# RDA1846.net
KiCad netlist of a schematic drawn in EAGLE
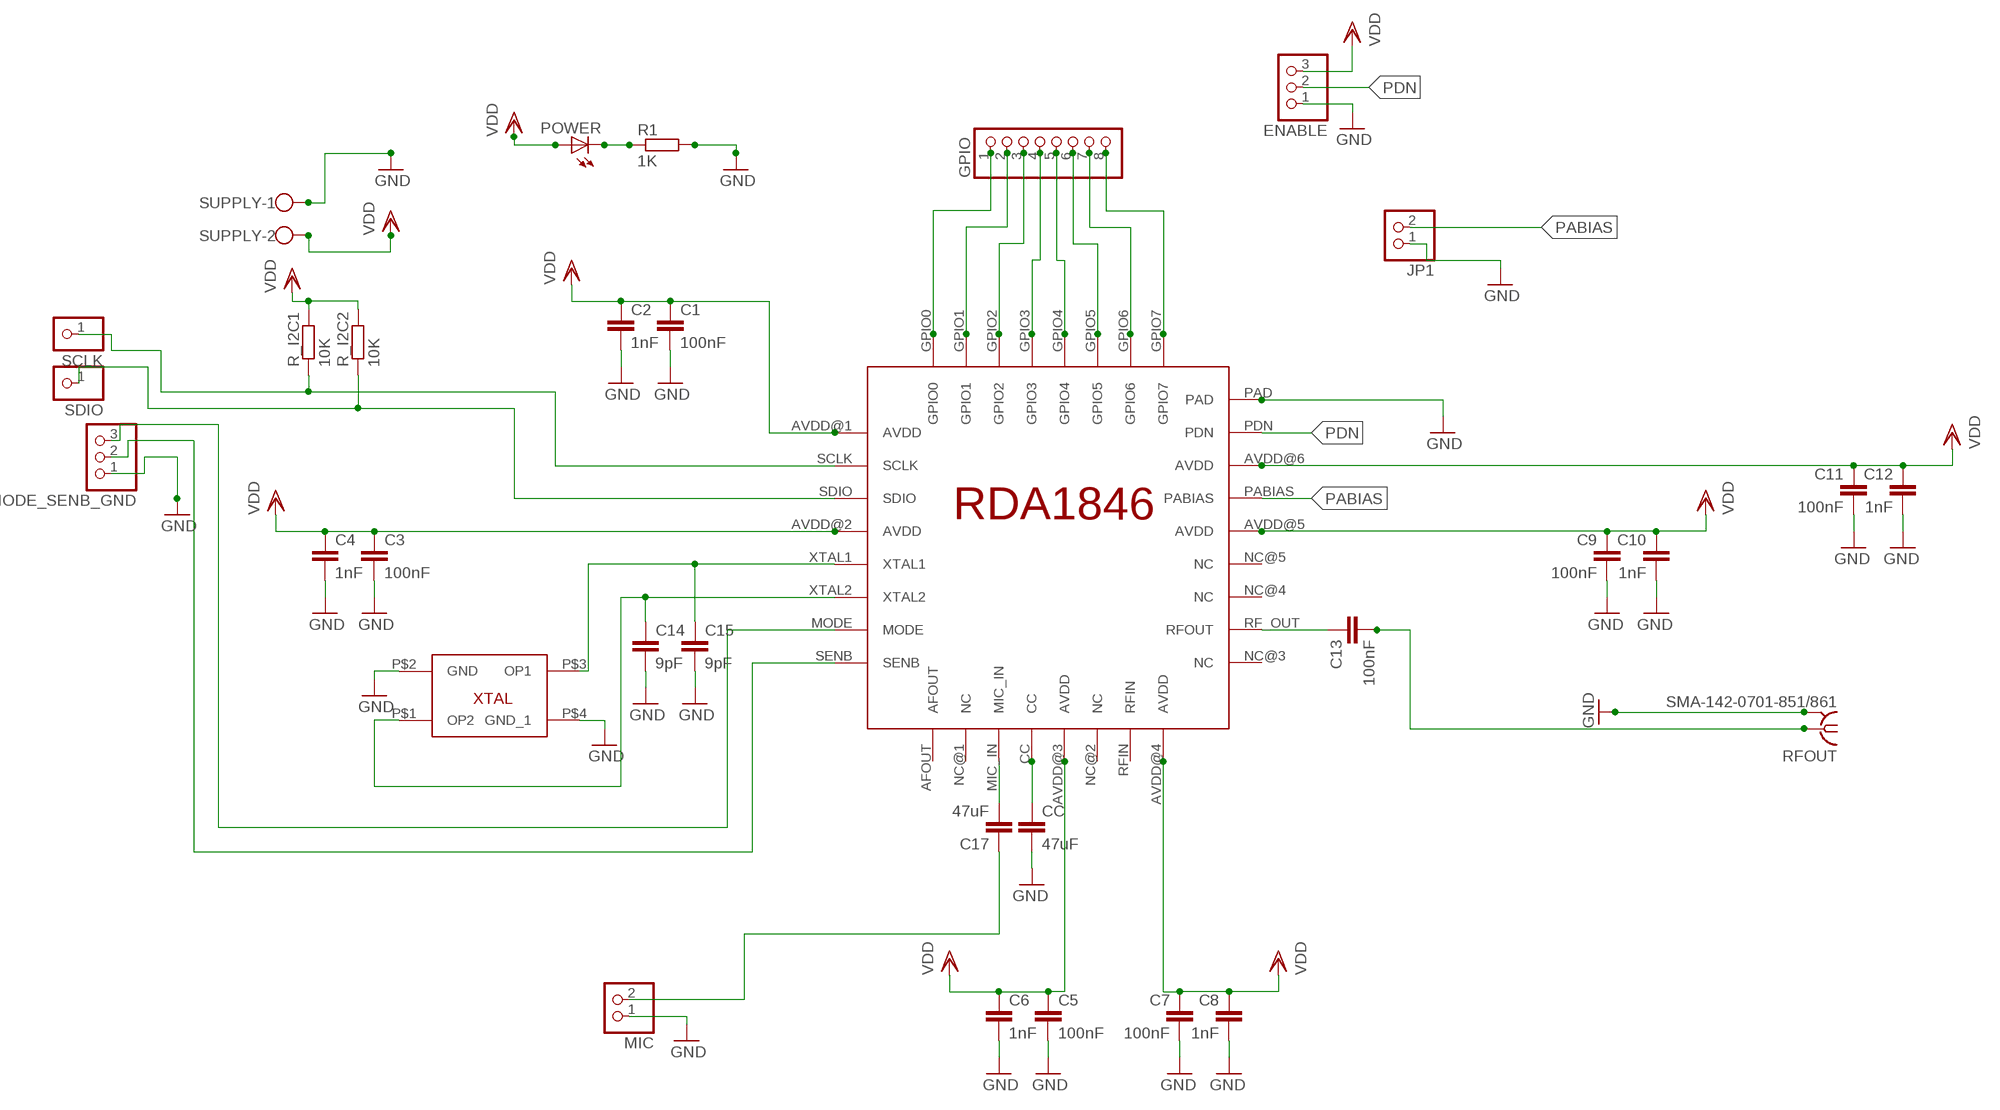
[diagram p0: schematic, sheet 1]
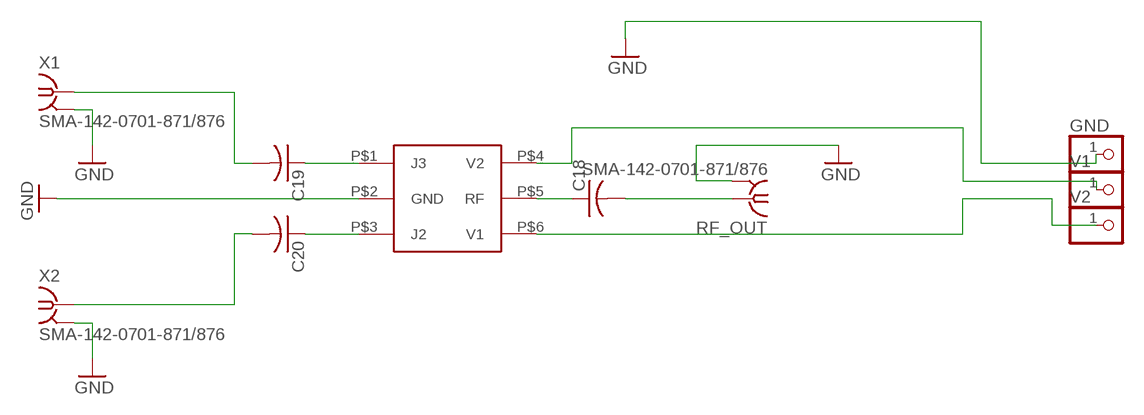
[diagram p1: schematic, sheet 2]

(export (version "E")
  (design (tool "Eeschema 10.0.6"))
  (components
    (comp (ref "C1")
      (value "100nF")
      (footprint "eagle-import:C0805")
      (libsource (lib "eagle-import") (part "C-EUC0805"))
    )
    (comp (ref "C2")
      (value "1nF")
      (footprint "eagle-import:C0805")
      (libsource (lib "eagle-import") (part "C-EUC0805"))
    )
    (comp (ref "C3")
      (value "100nF")
      (footprint "eagle-import:C0805")
      (libsource (lib "eagle-import") (part "C-EUC0805"))
    )
    (comp (ref "C4")
      (value "1nF")
      (footprint "eagle-import:C0805")
      (libsource (lib "eagle-import") (part "C-EUC0805"))
    )
    (comp (ref "C5")
      (value "100nF")
      (footprint "eagle-import:C0805")
      (libsource (lib "eagle-import") (part "C-EUC0805"))
    )
    (comp (ref "C6")
      (value "1nF")
      (footprint "eagle-import:C0805")
      (libsource (lib "eagle-import") (part "C-EUC0805"))
    )
    (comp (ref "C7")
      (value "100nF")
      (footprint "eagle-import:C0805")
      (libsource (lib "eagle-import") (part "C-EUC0805"))
    )
    (comp (ref "C8")
      (value "1nF")
      (footprint "eagle-import:C0805")
      (libsource (lib "eagle-import") (part "C-EUC0805"))
    )
    (comp (ref "C9")
      (value "100nF")
      (footprint "eagle-import:C0805")
      (libsource (lib "eagle-import") (part "C-EUC0805"))
    )
    (comp (ref "C10")
      (value "1nF")
      (footprint "eagle-import:C0805")
      (libsource (lib "eagle-import") (part "C-EUC0805"))
    )
    (comp (ref "C11")
      (value "100nF")
      (footprint "eagle-import:C0805")
      (libsource (lib "eagle-import") (part "C-EUC0805"))
    )
    (comp (ref "C12")
      (value "1nF")
      (footprint "eagle-import:C0805")
      (libsource (lib "eagle-import") (part "C-EUC0805"))
    )
    (comp (ref "C13")
      (value "100nF")
      (footprint "eagle-import:C0805")
      (libsource (lib "eagle-import") (part "C-EUC0805"))
    )
    (comp (ref "C14")
      (value "9pF")
      (footprint "eagle-import:C0805")
      (libsource (lib "eagle-import") (part "C-EUC0805"))
    )
    (comp (ref "C15")
      (value "9pF")
      (footprint "eagle-import:C0805")
      (libsource (lib "eagle-import") (part "C-EUC0805"))
    )
    (comp (ref "C17")
      (value "47uF")
      (footprint "eagle-import:C0805")
      (libsource (lib "eagle-import") (part "C-EUC0805"))
    )
    (comp (ref "CC")
      (value "47uF")
      (footprint "eagle-import:C0805")
      (libsource (lib "eagle-import") (part "C-EUC0805"))
    )
    (comp (ref "ENABLE")
      (value "PINHD-1X3")
      (footprint "eagle-import:1X03")
      (libsource (lib "eagle-import") (part "PINHD-1X3"))
    )
    (comp (ref "GPIO")
      (value "PINHD-1X8CLEANBIG")
      (footprint "eagle-import:1X08-CLEANBIG")
      (libsource (lib "eagle-import") (part "PINHD-1X8CLEANBIG"))
    )
    (comp (ref "JP1")
      (value "PINHD-1X2")
      (footprint "eagle-import:1X02")
      (libsource (lib "eagle-import") (part "PINHD-1X2"))
    )
    (comp (ref "MIC")
      (value "PINHD-1X2")
      (footprint "eagle-import:1X02")
      (libsource (lib "eagle-import") (part "PINHD-1X2"))
    )
    (comp (ref "MODE_SENB_GND")
      (value "PINHD-1X3")
      (footprint "eagle-import:1X03")
      (libsource (lib "eagle-import") (part "PINHD-1X3"))
    )
    (comp (ref "POWER")
      (value "LEDCHIPLED_1206")
      (footprint "eagle-import:CHIPLED_1206")
      (libsource (lib "eagle-import") (part "LEDCHIPLED_1206"))
    )
    (comp (ref "R1")
      (value "1K")
      (footprint "eagle-import:R0805")
      (libsource (lib "eagle-import") (part "R-EU_R0805"))
    )
    (comp (ref "RFOUT")
      (value "SMA-142-0701-851/861")
      (footprint "eagle-import:J502-ND-142-0701-851_861")
      (fields (field (name "MF") "JOHNSON COMPONENTS") (field (name "MPN") "142-0701-851"))
      (libsource (lib "eagle-import") (part "SMA-142-0701-851/861"))
    )
    (comp (ref "R_I2C1")
      (value "10K")
      (footprint "eagle-import:R0805")
      (libsource (lib "eagle-import") (part "R-EU_R0805"))
    )
    (comp (ref "R_I2C2")
      (value "10K")
      (footprint "eagle-import:R0805")
      (libsource (lib "eagle-import") (part "R-EU_R0805"))
    )
    (comp (ref "SCLK")
      (value "PINHD-1X1")
      (footprint "eagle-import:1X01")
      (libsource (lib "eagle-import") (part "PINHD-1X1"))
    )
    (comp (ref "SDIO")
      (value "PINHD-1X1")
      (footprint "eagle-import:1X01")
      (libsource (lib "eagle-import") (part "PINHD-1X1"))
    )
    (comp (ref "SUPPLY")
      (value "W237-102")
      (footprint "eagle-import:W237-102")
      (fields (field (name "MPN") "237-102"))
      (libsource (lib "eagle-import") (part "W237-102"))
    )
    (comp (ref "U$1")
      (value "RDA1846")
      (footprint "eagle-import:32_PIN_QFN")
      (libsource (lib "eagle-import") (part "RDA1846"))
    )
    (comp (ref "U$2")
      (value "CRYSTAL_FA_128")
      (footprint "eagle-import:FA_128")
      (libsource (lib "eagle-import") (part "CRYSTAL_FA_128"))
    )
    (comp (ref "C18")
      (value "C-USC1206")
      (footprint "eagle-import:C1206")
      (libsource (lib "eagle-import") (part "C-USC1206"))
    )
    (comp (ref "C19")
      (value "C-USC1206")
      (footprint "eagle-import:C1206")
      (libsource (lib "eagle-import") (part "C-USC1206"))
    )
    (comp (ref "C20")
      (value "C-USC1206")
      (footprint "eagle-import:C1206")
      (libsource (lib "eagle-import") (part "C-USC1206"))
    )
    (comp (ref "GND")
      (value "PINHD-1X1")
      (footprint "eagle-import:1X01")
      (libsource (lib "eagle-import") (part "pinhead_PINHD-1X1"))
    )
    (comp (ref "RF_OUT")
      (value "SMA-142-0701-871/876")
      (footprint "eagle-import:J502-ND-142-0701-871_876")
      (fields (field (name "MF") "JOHNSON COMPONENTS") (field (name "MPN") "142-0701-871"))
      (libsource (lib "eagle-import") (part "SMA-142-0701-871/876"))
    )
    (comp (ref "U$3")
      (value "RF_SWITCH")
      (footprint "eagle-import:SC90")
      (libsource (lib "eagle-import") (part "RF_SWITCH"))
    )
    (comp (ref "V1")
      (value "PINHD-1X1")
      (footprint "eagle-import:1X01")
      (libsource (lib "eagle-import") (part "pinhead_PINHD-1X1"))
    )
    (comp (ref "V2")
      (value "PINHD-1X1")
      (footprint "eagle-import:1X01")
      (libsource (lib "eagle-import") (part "pinhead_PINHD-1X1"))
    )
    (comp (ref "X1")
      (value "SMA-142-0701-871/876")
      (footprint "eagle-import:J502-ND-142-0701-871_876")
      (fields (field (name "MF") "JOHNSON COMPONENTS") (field (name "MPN") "142-0701-871"))
      (libsource (lib "eagle-import") (part "SMA-142-0701-871/876"))
    )
    (comp (ref "X2")
      (value "SMA-142-0701-871/876")
      (footprint "eagle-import:J502-ND-142-0701-871_876")
      (fields (field (name "MF") "JOHNSON COMPONENTS") (field (name "MPN") "142-0701-871"))
      (libsource (lib "eagle-import") (part "SMA-142-0701-871/876"))
    )
  )
  (nets
    (net (code "1") (name "GND") (class "Default")
      (node (ref "C1") (pin "2") (pinfunction "2_2") (pintype "passive"))
      (node (ref "C10") (pin "2") (pinfunction "2_2") (pintype "passive"))
      (node (ref "C11") (pin "2") (pinfunction "2_2") (pintype "passive"))
      (node (ref "C12") (pin "2") (pinfunction "2_2") (pintype "passive"))
      (node (ref "C14") (pin "2") (pinfunction "2_2") (pintype "passive"))
      (node (ref "C15") (pin "2") (pinfunction "2_2") (pintype "passive"))
      (node (ref "C2") (pin "2") (pinfunction "2_2") (pintype "passive"))
      (node (ref "C3") (pin "2") (pinfunction "2_2") (pintype "passive"))
      (node (ref "C4") (pin "2") (pinfunction "2_2") (pintype "passive"))
      (node (ref "C5") (pin "2") (pinfunction "2_2") (pintype "passive"))
      (node (ref "C6") (pin "2") (pinfunction "2_2") (pintype "passive"))
      (node (ref "C7") (pin "2") (pinfunction "2_2") (pintype "passive"))
      (node (ref "C8") (pin "2") (pinfunction "2_2") (pintype "passive"))
      (node (ref "C9") (pin "2") (pinfunction "2_2") (pintype "passive"))
      (node (ref "CC") (pin "2") (pinfunction "2_2") (pintype "passive"))
      (node (ref "ENABLE") (pin "1") (pinfunction "1_1") (pintype "passive"))
      (node (ref "GND") (pin "1") (pinfunction "1_1") (pintype "passive"))
      (node (ref "JP1") (pin "1") (pinfunction "1_1") (pintype "passive"))
      (node (ref "MIC") (pin "1") (pinfunction "1_1") (pintype "passive"))
      (node (ref "MODE_SENB_GND") (pin "1") (pinfunction "1_1") (pintype "passive"))
      (node (ref "R1") (pin "2") (pinfunction "2_2") (pintype "passive"))
      (node (ref "RFOUT") (pin "G@1") (pinfunction "2_G@1") (pintype "passive"))
      (node (ref "RFOUT") (pin "G@2") (pinfunction "2_G@2") (pintype "passive"))
      (node (ref "RFOUT") (pin "G@3") (pinfunction "2_G@3") (pintype "passive"))
      (node (ref "RFOUT") (pin "G@4") (pinfunction "2_G@4") (pintype "passive"))
      (node (ref "RF_OUT") (pin "G@1") (pinfunction "2_G@1") (pintype "passive"))
      (node (ref "RF_OUT") (pin "G@2") (pinfunction "2_G@2") (pintype "passive"))
      (node (ref "RF_OUT") (pin "G@3") (pinfunction "2_G@3") (pintype "passive"))
      (node (ref "RF_OUT") (pin "G@4") (pinfunction "2_G@4") (pintype "passive"))
      (node (ref "SUPPLY") (pin "1") (pinfunction "KL_1") (pintype "passive"))
      (node (ref "U$1") (pin "PAD") (pinfunction "PAD_PAD") (pintype "bidirectional"))
      (node (ref "U$2") (pin "P$2") (pinfunction "GND_P$2") (pintype "bidirectional"))
      (node (ref "U$2") (pin "P$4") (pinfunction "GND_1_P$4") (pintype "bidirectional"))
      (node (ref "U$3") (pin "P$2") (pinfunction "GND_P$2") (pintype "bidirectional"))
      (node (ref "X1") (pin "G@1") (pinfunction "2_G@1") (pintype "passive"))
      (node (ref "X1") (pin "G@2") (pinfunction "2_G@2") (pintype "passive"))
      (node (ref "X1") (pin "G@3") (pinfunction "2_G@3") (pintype "passive"))
      (node (ref "X1") (pin "G@4") (pinfunction "2_G@4") (pintype "passive"))
      (node (ref "X2") (pin "G@1") (pinfunction "2_G@1") (pintype "passive"))
      (node (ref "X2") (pin "G@2") (pinfunction "2_G@2") (pintype "passive"))
      (node (ref "X2") (pin "G@3") (pinfunction "2_G@3") (pintype "passive"))
      (node (ref "X2") (pin "G@4") (pinfunction "2_G@4") (pintype "passive"))
    )
    (net (code "2") (name "Net-(C13-Pad2)") (class "Default")
      (node (ref "C13") (pin "2") (pinfunction "2_2") (pintype "passive"))
      (node (ref "RFOUT") (pin "1") (pinfunction "1_1") (pintype "passive"))
    )
    (net (code "3") (name "Net-(C17-Pad1)") (class "Default")
      (node (ref "C17") (pin "1") (pinfunction "1_1") (pintype "passive"))
      (node (ref "MIC") (pin "2") (pinfunction "2_2") (pintype "passive"))
    )
    (net (code "4") (name "Net-(C17-Pad2)") (class "Default")
      (node (ref "C17") (pin "2") (pinfunction "2_2") (pintype "passive"))
      (node (ref "U$1") (pin "MIC_IN") (pinfunction "MIC_IN_MIC_IN") (pintype "bidirectional"))
    )
    (net (code "5") (name "Net-(C18-Pad2)") (class "Default")
      (node (ref "C18") (pin "2") (pinfunction "2_2") (pintype "passive"))
      (node (ref "RF_OUT") (pin "1") (pinfunction "1_1") (pintype "passive"))
    )
    (net (code "6") (name "Net-(C19-Pad2)") (class "Default")
      (node (ref "C19") (pin "2") (pinfunction "2_2") (pintype "passive"))
      (node (ref "X1") (pin "1") (pinfunction "1_1") (pintype "passive"))
    )
    (net (code "7") (name "Net-(C20-Pad2)") (class "Default")
      (node (ref "C20") (pin "2") (pinfunction "2_2") (pintype "passive"))
      (node (ref "X2") (pin "1") (pinfunction "1_1") (pintype "passive"))
    )
    (net (code "8") (name "Net-(CC-Pad1)") (class "Default")
      (node (ref "CC") (pin "1") (pinfunction "1_1") (pintype "passive"))
      (node (ref "U$1") (pin "CC") (pinfunction "CC_CC") (pintype "bidirectional"))
    )
    (net (code "9") (name "Net-(GPIO-Pad1)") (class "Default")
      (node (ref "GPIO") (pin "1") (pinfunction "1_1") (pintype "passive"))
      (node (ref "U$1") (pin "GPIO0") (pinfunction "GPIO0_GPIO0") (pintype "bidirectional"))
    )
    (net (code "10") (name "Net-(GPIO-Pad2)") (class "Default")
      (node (ref "GPIO") (pin "2") (pinfunction "2_2") (pintype "passive"))
      (node (ref "U$1") (pin "GPIO1") (pinfunction "GPIO1_GPIO1") (pintype "bidirectional"))
    )
    (net (code "11") (name "Net-(GPIO-Pad3)") (class "Default")
      (node (ref "GPIO") (pin "3") (pinfunction "3_3") (pintype "passive"))
      (node (ref "U$1") (pin "GPIO2") (pinfunction "GPIO2_GPIO2") (pintype "bidirectional"))
    )
    (net (code "12") (name "Net-(GPIO-Pad4)") (class "Default")
      (node (ref "GPIO") (pin "4") (pinfunction "4_4") (pintype "passive"))
      (node (ref "U$1") (pin "GPIO3") (pinfunction "GPIO3_GPIO3") (pintype "bidirectional"))
    )
    (net (code "13") (name "Net-(GPIO-Pad5)") (class "Default")
      (node (ref "GPIO") (pin "5") (pinfunction "5_5") (pintype "passive"))
      (node (ref "U$1") (pin "GPIO4") (pinfunction "GPIO4_GPIO4") (pintype "bidirectional"))
    )
    (net (code "14") (name "Net-(GPIO-Pad6)") (class "Default")
      (node (ref "GPIO") (pin "6") (pinfunction "6_6") (pintype "passive"))
      (node (ref "U$1") (pin "GPIO5") (pinfunction "GPIO5_GPIO5") (pintype "bidirectional"))
    )
    (net (code "15") (name "Net-(GPIO-Pad7)") (class "Default")
      (node (ref "GPIO") (pin "7") (pinfunction "7_7") (pintype "passive"))
      (node (ref "U$1") (pin "GPIO6") (pinfunction "GPIO6_GPIO6") (pintype "bidirectional"))
    )
    (net (code "16") (name "Net-(GPIO-Pad8)") (class "Default")
      (node (ref "GPIO") (pin "8") (pinfunction "8_8") (pintype "passive"))
      (node (ref "U$1") (pin "GPIO7") (pinfunction "GPIO7_GPIO7") (pintype "bidirectional"))
    )
    (net (code "17") (name "Net-(MODE_SENB_GND-Pad2)") (class "Default")
      (node (ref "MODE_SENB_GND") (pin "2") (pinfunction "2_2") (pintype "passive"))
      (node (ref "U$1") (pin "SENB") (pinfunction "SENB_SENB") (pintype "bidirectional"))
    )
    (net (code "18") (name "Net-(MODE_SENB_GND-Pad3)") (class "Default")
      (node (ref "MODE_SENB_GND") (pin "3") (pinfunction "3_3") (pintype "passive"))
      (node (ref "U$1") (pin "MODE") (pinfunction "MODE_MODE") (pintype "bidirectional"))
    )
    (net (code "19") (name "Net-(POWER-PadC)") (class "Default")
      (node (ref "POWER") (pin "C") (pinfunction "C_C") (pintype "passive"))
      (node (ref "R1") (pin "1") (pinfunction "1_1") (pintype "passive"))
    )
    (net (code "20") (name "Net-(R_I2C1-Pad1)") (class "Default")
      (node (ref "R_I2C1") (pin "1") (pinfunction "1_1") (pintype "passive"))
      (node (ref "SCLK") (pin "1") (pinfunction "1_1") (pintype "passive"))
      (node (ref "U$1") (pin "SCLK") (pinfunction "SCLK_SCLK") (pintype "bidirectional"))
    )
    (net (code "21") (name "Net-(R_I2C2-Pad1)") (class "Default")
      (node (ref "R_I2C2") (pin "1") (pinfunction "1_1") (pintype "passive"))
      (node (ref "SDIO") (pin "1") (pinfunction "1_1") (pintype "passive"))
      (node (ref "U$1") (pin "SDIO") (pinfunction "SDIO_SDIO") (pintype "bidirectional"))
    )
    (net (code "22") (name "Net-(U$1-RFOUT)") (class "Default")
      (node (ref "C13") (pin "1") (pinfunction "1_1") (pintype "passive"))
      (node (ref "U$1") (pin "RF_OUT") (pinfunction "RFOUT_RF_OUT") (pintype "bidirectional"))
    )
    (net (code "23") (name "Net-(U$2-OP1)") (class "Default")
      (node (ref "C15") (pin "1") (pinfunction "1_1") (pintype "passive"))
      (node (ref "U$1") (pin "XTAL1") (pinfunction "XTAL1_XTAL1") (pintype "bidirectional"))
      (node (ref "U$2") (pin "P$3") (pinfunction "OP1_P$3") (pintype "bidirectional"))
    )
    (net (code "24") (name "Net-(U$2-OP2)") (class "Default")
      (node (ref "C14") (pin "1") (pinfunction "1_1") (pintype "passive"))
      (node (ref "U$1") (pin "XTAL2") (pinfunction "XTAL2_XTAL2") (pintype "bidirectional"))
      (node (ref "U$2") (pin "P$1") (pinfunction "OP2_P$1") (pintype "bidirectional"))
    )
    (net (code "25") (name "Net-(U$3-J2)") (class "Default")
      (node (ref "C20") (pin "1") (pinfunction "1_1") (pintype "passive"))
      (node (ref "U$3") (pin "P$3") (pinfunction "J2_P$3") (pintype "bidirectional"))
    )
    (net (code "26") (name "Net-(U$3-J3)") (class "Default")
      (node (ref "C19") (pin "1") (pinfunction "1_1") (pintype "passive"))
      (node (ref "U$3") (pin "P$1") (pinfunction "J3_P$1") (pintype "bidirectional"))
    )
    (net (code "27") (name "Net-(U$3-RF)") (class "Default")
      (node (ref "C18") (pin "1") (pinfunction "1_1") (pintype "passive"))
      (node (ref "U$3") (pin "P$5") (pinfunction "RF_P$5") (pintype "bidirectional"))
    )
    (net (code "28") (name "Net-(U$3-V1)") (class "Default")
      (node (ref "U$3") (pin "P$6") (pinfunction "V1_P$6") (pintype "bidirectional"))
      (node (ref "V2") (pin "1") (pinfunction "1_1") (pintype "passive"))
    )
    (net (code "29") (name "Net-(U$3-V2)") (class "Default")
      (node (ref "U$3") (pin "P$4") (pinfunction "V2_P$4") (pintype "bidirectional"))
      (node (ref "V1") (pin "1") (pinfunction "1_1") (pintype "passive"))
    )
    (net (code "30") (name "PABIAS") (class "Default")
      (node (ref "JP1") (pin "2") (pinfunction "2_2") (pintype "passive"))
      (node (ref "U$1") (pin "PABIAS") (pinfunction "PABIAS_PABIAS") (pintype "bidirectional"))
    )
    (net (code "31") (name "PDN") (class "Default")
      (node (ref "ENABLE") (pin "2") (pinfunction "2_2") (pintype "passive"))
      (node (ref "U$1") (pin "PDN") (pinfunction "PDN_PDN") (pintype "bidirectional"))
    )
    (net (code "32") (name "VDD") (class "Default")
      (node (ref "C1") (pin "1") (pinfunction "1_1") (pintype "passive"))
      (node (ref "C10") (pin "1") (pinfunction "1_1") (pintype "passive"))
      (node (ref "C11") (pin "1") (pinfunction "1_1") (pintype "passive"))
      (node (ref "C12") (pin "1") (pinfunction "1_1") (pintype "passive"))
      (node (ref "C2") (pin "1") (pinfunction "1_1") (pintype "passive"))
      (node (ref "C3") (pin "1") (pinfunction "1_1") (pintype "passive"))
      (node (ref "C4") (pin "1") (pinfunction "1_1") (pintype "passive"))
      (node (ref "C5") (pin "1") (pinfunction "1_1") (pintype "passive"))
      (node (ref "C6") (pin "1") (pinfunction "1_1") (pintype "passive"))
      (node (ref "C7") (pin "1") (pinfunction "1_1") (pintype "passive"))
      (node (ref "C8") (pin "1") (pinfunction "1_1") (pintype "passive"))
      (node (ref "C9") (pin "1") (pinfunction "1_1") (pintype "passive"))
      (node (ref "ENABLE") (pin "3") (pinfunction "3_3") (pintype "passive"))
      (node (ref "POWER") (pin "A") (pinfunction "A_A") (pintype "passive"))
      (node (ref "R_I2C1") (pin "2") (pinfunction "2_2") (pintype "passive"))
      (node (ref "R_I2C2") (pin "2") (pinfunction "2_2") (pintype "passive"))
      (node (ref "SUPPLY") (pin "2") (pinfunction "KL_2") (pintype "passive"))
      (node (ref "U$1") (pin "AVDD@1") (pinfunction "AVDD_AVDD@1") (pintype "bidirectional"))
      (node (ref "U$1") (pin "AVDD@2") (pinfunction "AVDD_AVDD@2") (pintype "bidirectional"))
      (node (ref "U$1") (pin "AVDD@3") (pinfunction "AVDD_AVDD@3") (pintype "bidirectional"))
      (node (ref "U$1") (pin "AVDD@4") (pinfunction "AVDD_AVDD@4") (pintype "bidirectional"))
      (node (ref "U$1") (pin "AVDD@5") (pinfunction "AVDD_AVDD@5") (pintype "bidirectional"))
      (node (ref "U$1") (pin "AVDD@6") (pinfunction "AVDD_AVDD@6") (pintype "bidirectional"))
    )
    (net (code "33") (name "unconnected-(U$1-NC-PadNC@1)") (class "Default")
      (node (ref "U$1") (pin "NC@1") (pinfunction "NC_NC@1") (pintype "bidirectional"))
    )
    (net (code "34") (name "unconnected-(U$1-NC-PadNC@2)") (class "Default")
      (node (ref "U$1") (pin "NC@2") (pinfunction "NC_NC@2") (pintype "bidirectional"))
    )
    (net (code "35") (name "unconnected-(U$1-NC-PadNC@3)") (class "Default")
      (node (ref "U$1") (pin "NC@3") (pinfunction "NC_NC@3") (pintype "bidirectional"))
    )
    (net (code "36") (name "unconnected-(U$1-NC-PadNC@4)") (class "Default")
      (node (ref "U$1") (pin "NC@4") (pinfunction "NC_NC@4") (pintype "bidirectional"))
    )
    (net (code "37") (name "unconnected-(U$1-NC-PadNC@5)") (class "Default")
      (node (ref "U$1") (pin "NC@5") (pinfunction "NC_NC@5") (pintype "bidirectional"))
    )
    (net (code "38") (name "unconnected-(U$1-PadAFOUT)") (class "Default")
      (node (ref "U$1") (pin "AFOUT") (pinfunction "AFOUT_AFOUT") (pintype "bidirectional"))
    )
    (net (code "39") (name "unconnected-(U$1-PadRFIN)") (class "Default")
      (node (ref "U$1") (pin "RFIN") (pinfunction "RFIN_RFIN") (pintype "bidirectional"))
    )
  )
)
